# SCH_Self-balancing_2024-06-14.net
KiCad netlist of a schematic drawn in EasyEDA
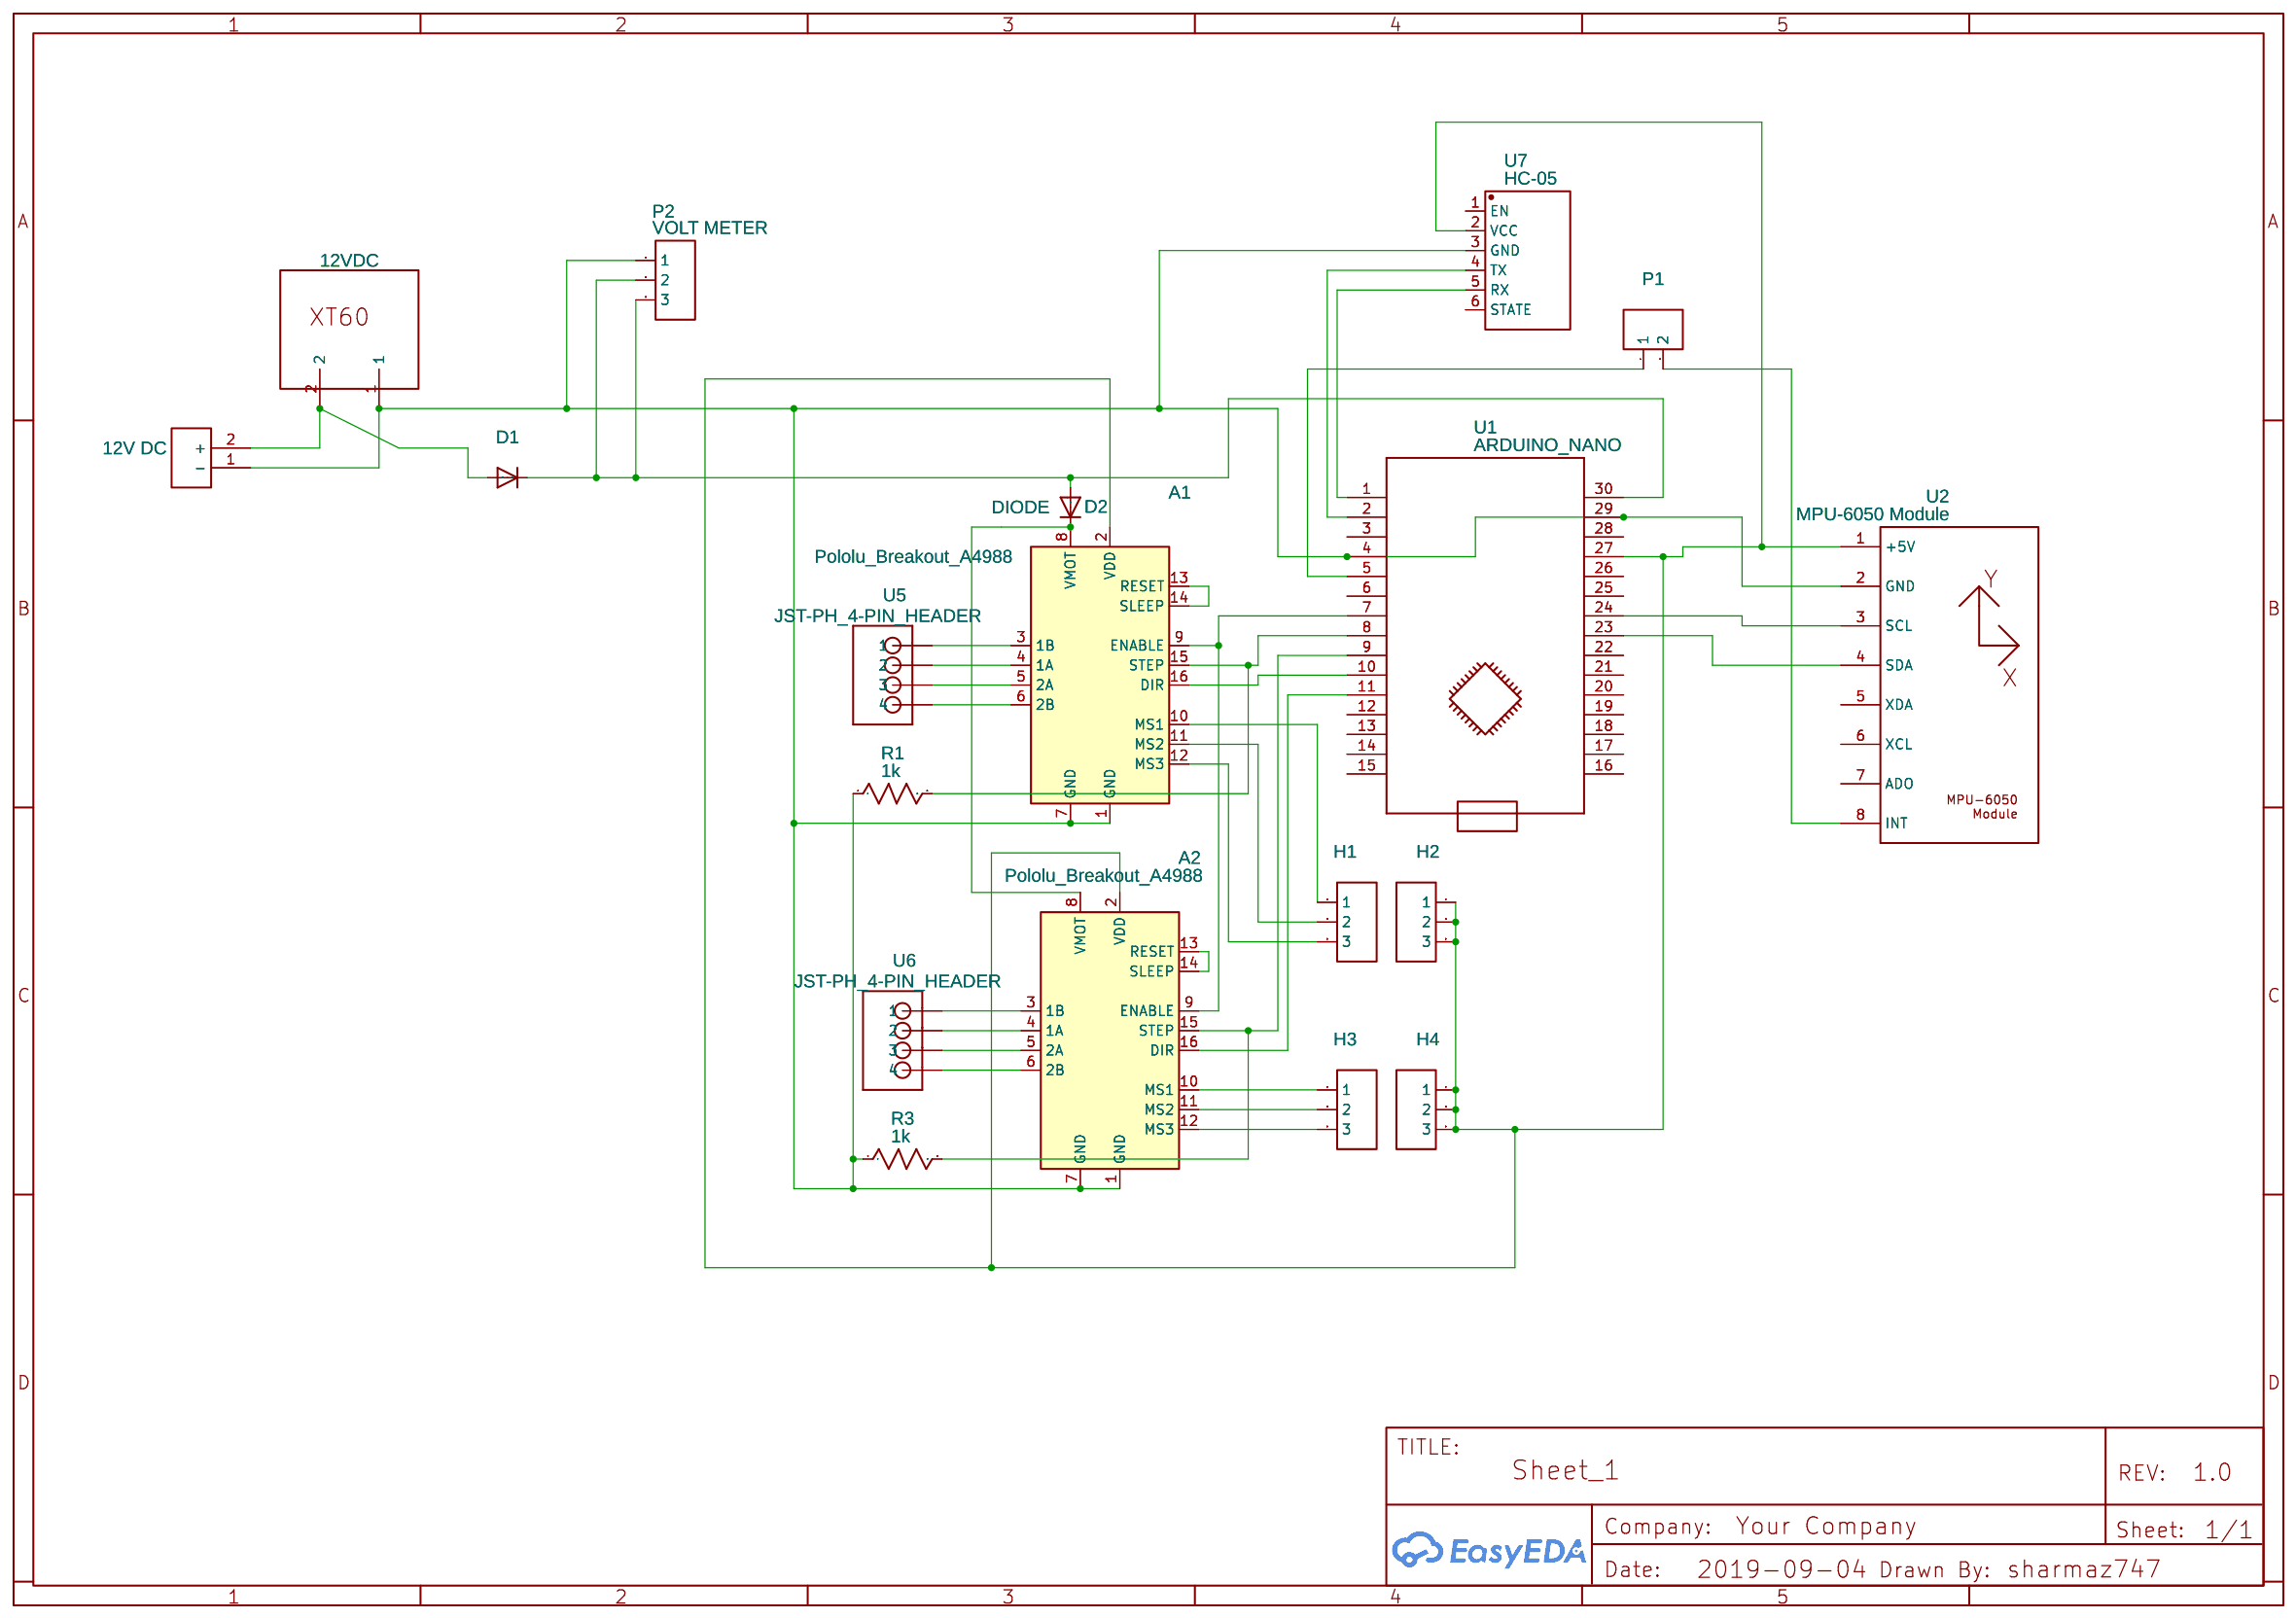
[diagram p0: schematic sheet]

(export (version "E")
  (design (tool "Eeschema 10.0.6"))
  (components
    (comp (ref "12VDC") (value "XT60") (libsource (lib "") (part "Unknown_145_200")))
    (comp (ref "24VDC")
      (value "12V DC")
      (fields (field (name "Manufacturer Part") "SCREW TERMINAL 6P .2"))
      (libsource (lib "") (part "Unknown_120_240"))
    )
    (comp (ref "A1") (value "Pololu_Breakout_A4988") (libsource (lib "") (part "Unknown_550_335")))
    (comp (ref "A2") (value "Pololu_Breakout_A4988") (libsource (lib "") (part "Unknown_555_520")))
    (comp (ref "D1") (value "DIODE") (libsource (lib "") (part "Unknown_250_235")))
    (comp (ref "D2") (value "DIODE") (libsource (lib "") (part "Unknown_535_250")))
    (comp (ref "H1")
      (value "Header-Male-2.54_1x3")
      (fields (field (name "Manufacturer Part") "Header2.54mm 1*3P") (field (name "Manufacturer") "BOOMELE"))
      (libsource (lib "") (part "Unknown_675_460"))
    )
    (comp (ref "H2")
      (value "Header-Male-2.54_1x3")
      (fields (field (name "Manufacturer Part") "Header2.54mm 1*3P") (field (name "Manufacturer") "BOOMELE"))
      (libsource (lib "") (part "Unknown_715_460"))
    )
    (comp (ref "H3")
      (value "Header-Male-2.54_1x3")
      (fields (field (name "Manufacturer Part") "Header2.54mm 1*3P") (field (name "Manufacturer") "BOOMELE"))
      (libsource (lib "") (part "Unknown_675_555"))
    )
    (comp (ref "H4")
      (value "Header-Male-2.54_1x3")
      (fields (field (name "Manufacturer Part") "Header2.54mm 1*3P") (field (name "Manufacturer") "BOOMELE"))
      (libsource (lib "") (part "Unknown_715_555"))
    )
    (comp (ref "P1")
      (value "Header-Female-2.54_1x2")
      (fields (field (name "Manufacturer Part") "2.54-1*2PFemale") (field (name "Manufacturer") "BOOMELE"))
      (libsource (lib "") (part "Unknown_830_165"))
    )
    (comp (ref "P2")
      (value "VOLT METER")
      (fields
        (field (name "Manufacturer Part") "Header-Female-2.54_1x3")
        (field (name "Manufacturer") "Boom Precision Elec")
      )
      (libsource (lib "") (part "Unknown_330_135"))
    )
    (comp (ref "R1") (value "1k") (libsource (lib "") (part "Res_AXIAL-0.3(1/8W)_US")))
    (comp (ref "R3") (value "1k") (libsource (lib "") (part "Res_AXIAL-0.3(1/8W)_US")))
    (comp (ref "U1") (value "ARDUINO_NANO") (libsource (lib "") (part "Unknown_745_320")))
    (comp (ref "U2") (value "MPU-6050 Module") (libsource (lib "") (part "Unknown_975_340")))
    (comp (ref "U5") (value "JST-PH_4-PIN_HEADER") (libsource (lib "") (part "Unknown_445_335")))
    (comp (ref "U6") (value "JST-PH_4-PIN_HEADER") (libsource (lib "") (part "Unknown_450_520")))
    (comp (ref "U7") (value "HC-05") (libsource (lib "") (part "Unknown_745_90")))
  )
  (nets
    (net (code "1") (name "Net-(24VDC-+)") (class "Default")
      (node (ref "12VDC") (pin "2") (pinfunction "2_2") (pintype "unspecified"))
      (node (ref "24VDC") (pin "2") (pinfunction "+_2") (pintype "unspecified"))
      (node (ref "D1") (pin "A") (pinfunction "A_A") (pintype "unspecified"))
    )
    (net (code "2") (name "Net-(24VDC--)") (class "Default")
      (node (ref "12VDC") (pin "1") (pinfunction "1_1") (pintype "unspecified"))
      (node (ref "24VDC") (pin "1") (pinfunction "-_1") (pintype "unspecified"))
      (node (ref "A1") (pin "1") (pinfunction "GND_1") (pintype "bidirectional"))
      (node (ref "A1") (pin "7") (pinfunction "GND_7") (pintype "bidirectional"))
      (node (ref "A2") (pin "1") (pinfunction "GND_1") (pintype "bidirectional"))
      (node (ref "A2") (pin "7") (pinfunction "GND_7") (pintype "bidirectional"))
      (node (ref "P2") (pin "1") (pinfunction "1_1") (pintype "input"))
      (node (ref "R1") (pin "1") (pinfunction "1_1") (pintype "unspecified"))
      (node (ref "R3") (pin "1") (pinfunction "1_1") (pintype "unspecified"))
      (node (ref "U1") (pin "29") (pintype "unspecified"))
      (node (ref "U1") (pin "4") (pintype "unspecified"))
      (node (ref "U2") (pin "2") (pinfunction "GND_2") (pintype "unspecified"))
      (node (ref "U7") (pin "3") (pinfunction "GND_3") (pintype "unspecified"))
    )
    (net (code "3") (name "Net-(A1-1A)") (class "Default")
      (node (ref "A1") (pin "4") (pinfunction "1A_4") (pintype "output"))
      (node (ref "U5") (pin "P2") (pinfunction "2_P2") (pintype "unspecified"))
    )
    (net (code "4") (name "Net-(A1-1B)") (class "Default")
      (node (ref "A1") (pin "3") (pinfunction "1B_3") (pintype "output"))
      (node (ref "U5") (pin "P1") (pinfunction "1_P1") (pintype "unspecified"))
    )
    (net (code "5") (name "Net-(A1-2A)") (class "Default")
      (node (ref "A1") (pin "5") (pinfunction "2A_5") (pintype "output"))
      (node (ref "U5") (pin "P3") (pinfunction "3_P3") (pintype "unspecified"))
    )
    (net (code "6") (name "Net-(A1-2B)") (class "Default")
      (node (ref "A1") (pin "6") (pinfunction "2B_6") (pintype "output"))
      (node (ref "U5") (pin "P4") (pinfunction "4_P4") (pintype "unspecified"))
    )
    (net (code "7") (name "Net-(A1-DIR)") (class "Default")
      (node (ref "A1") (pin "16") (pinfunction "DIR_16") (pintype "input"))
      (node (ref "U1") (pin "10") (pintype "unspecified"))
    )
    (net (code "8") (name "Net-(A1-ENABLE)") (class "Default")
      (node (ref "A1") (pin "9") (pinfunction "ENABLE_9") (pintype "input"))
      (node (ref "A2") (pin "9") (pinfunction "ENABLE_9") (pintype "input"))
      (node (ref "U1") (pin "7") (pintype "unspecified"))
    )
    (net (code "9") (name "Net-(A1-MS1)") (class "Default")
      (node (ref "A1") (pin "10") (pinfunction "MS1_10") (pintype "input"))
      (node (ref "H1") (pin "1") (pinfunction "1_1") (pintype "input"))
    )
    (net (code "10") (name "Net-(A1-MS2)") (class "Default")
      (node (ref "A1") (pin "11") (pinfunction "MS2_11") (pintype "input"))
      (node (ref "H1") (pin "2") (pinfunction "2_2") (pintype "input"))
    )
    (net (code "11") (name "Net-(A1-MS3)") (class "Default")
      (node (ref "A1") (pin "12") (pinfunction "MS3_12") (pintype "input"))
      (node (ref "H1") (pin "3") (pinfunction "3_3") (pintype "input"))
    )
    (net (code "12") (name "Net-(A1-RESET)") (class "Default")
      (node (ref "A1") (pin "13") (pinfunction "RESET_13") (pintype "input"))
      (node (ref "A1") (pin "14") (pinfunction "SLEEP_14") (pintype "input"))
    )
    (net (code "13") (name "Net-(A1-STEP)") (class "Default")
      (node (ref "A1") (pin "15") (pinfunction "STEP_15") (pintype "input"))
      (node (ref "R1") (pin "2") (pinfunction "2_2") (pintype "unspecified"))
      (node (ref "U1") (pin "8") (pintype "unspecified"))
    )
    (net (code "14") (name "Net-(A1-VDD)") (class "Default")
      (node (ref "A1") (pin "2") (pinfunction "VDD_2") (pintype "bidirectional"))
      (node (ref "A2") (pin "2") (pinfunction "VDD_2") (pintype "bidirectional"))
      (node (ref "H2") (pin "1") (pinfunction "1_1") (pintype "input"))
      (node (ref "H2") (pin "2") (pinfunction "2_2") (pintype "input"))
      (node (ref "H2") (pin "3") (pinfunction "3_3") (pintype "input"))
      (node (ref "H4") (pin "1") (pinfunction "1_1") (pintype "input"))
      (node (ref "H4") (pin "2") (pinfunction "2_2") (pintype "input"))
      (node (ref "H4") (pin "3") (pinfunction "3_3") (pintype "input"))
      (node (ref "U1") (pin "27") (pintype "unspecified"))
      (node (ref "U2") (pin "1") (pinfunction "+5V_1") (pintype "unspecified"))
      (node (ref "U7") (pin "2") (pinfunction "VCC_2") (pintype "unspecified"))
    )
    (net (code "15") (name "Net-(A1-VMOT)") (class "Default")
      (node (ref "A1") (pin "8") (pinfunction "VMOT_8") (pintype "bidirectional"))
      (node (ref "A2") (pin "8") (pinfunction "VMOT_8") (pintype "bidirectional"))
      (node (ref "D2") (pin "C") (pinfunction "C_C") (pintype "unspecified"))
    )
    (net (code "16") (name "Net-(A2-1A)") (class "Default")
      (node (ref "A2") (pin "4") (pinfunction "1A_4") (pintype "output"))
      (node (ref "U6") (pin "P2") (pinfunction "2_P2") (pintype "unspecified"))
    )
    (net (code "17") (name "Net-(A2-1B)") (class "Default")
      (node (ref "A2") (pin "3") (pinfunction "1B_3") (pintype "output"))
      (node (ref "U6") (pin "P1") (pinfunction "1_P1") (pintype "unspecified"))
    )
    (net (code "18") (name "Net-(A2-2A)") (class "Default")
      (node (ref "A2") (pin "5") (pinfunction "2A_5") (pintype "output"))
      (node (ref "U6") (pin "P3") (pinfunction "3_P3") (pintype "unspecified"))
    )
    (net (code "19") (name "Net-(A2-2B)") (class "Default")
      (node (ref "A2") (pin "6") (pinfunction "2B_6") (pintype "output"))
      (node (ref "U6") (pin "P4") (pinfunction "4_P4") (pintype "unspecified"))
    )
    (net (code "20") (name "Net-(A2-DIR)") (class "Default")
      (node (ref "A2") (pin "16") (pinfunction "DIR_16") (pintype "input"))
      (node (ref "U1") (pin "11") (pintype "unspecified"))
    )
    (net (code "21") (name "Net-(A2-MS1)") (class "Default")
      (node (ref "A2") (pin "10") (pinfunction "MS1_10") (pintype "input"))
      (node (ref "H3") (pin "1") (pinfunction "1_1") (pintype "input"))
    )
    (net (code "22") (name "Net-(A2-MS2)") (class "Default")
      (node (ref "A2") (pin "11") (pinfunction "MS2_11") (pintype "input"))
      (node (ref "H3") (pin "2") (pinfunction "2_2") (pintype "input"))
    )
    (net (code "23") (name "Net-(A2-MS3)") (class "Default")
      (node (ref "A2") (pin "12") (pinfunction "MS3_12") (pintype "input"))
      (node (ref "H3") (pin "3") (pinfunction "3_3") (pintype "input"))
    )
    (net (code "24") (name "Net-(A2-RESET)") (class "Default")
      (node (ref "A2") (pin "13") (pinfunction "RESET_13") (pintype "input"))
      (node (ref "A2") (pin "14") (pinfunction "SLEEP_14") (pintype "input"))
    )
    (net (code "25") (name "Net-(A2-STEP)") (class "Default")
      (node (ref "A2") (pin "15") (pinfunction "STEP_15") (pintype "input"))
      (node (ref "R3") (pin "2") (pinfunction "2_2") (pintype "unspecified"))
      (node (ref "U1") (pin "9") (pintype "unspecified"))
    )
    (net (code "26") (name "Net-(D1-PadC)") (class "Default")
      (node (ref "D1") (pin "C") (pinfunction "C_C") (pintype "unspecified"))
      (node (ref "D2") (pin "A") (pinfunction "A_A") (pintype "unspecified"))
      (node (ref "P2") (pin "2") (pinfunction "2_2") (pintype "input"))
      (node (ref "P2") (pin "3") (pinfunction "3_3") (pintype "input"))
      (node (ref "U1") (pin "30") (pintype "unspecified"))
    )
    (net (code "27") (name "Net-(P1-Pad1)") (class "Default")
      (node (ref "P1") (pin "1") (pinfunction "1_1") (pintype "input"))
      (node (ref "U1") (pin "5") (pintype "unspecified"))
    )
    (net (code "28") (name "Net-(U2-INT)") (class "Default")
      (node (ref "P1") (pin "2") (pinfunction "2_2") (pintype "input"))
      (node (ref "U2") (pin "8") (pinfunction "INT_8") (pintype "unspecified"))
    )
    (net (code "29") (name "Net-(U2-SCL)") (class "Default")
      (node (ref "U1") (pin "24") (pintype "unspecified"))
      (node (ref "U2") (pin "3") (pinfunction "SCL_3") (pintype "unspecified"))
    )
    (net (code "30") (name "Net-(U2-SDA)") (class "Default")
      (node (ref "U1") (pin "23") (pintype "unspecified"))
      (node (ref "U2") (pin "4") (pinfunction "SDA_4") (pintype "unspecified"))
    )
    (net (code "31") (name "Net-(U7-RX)") (class "Default")
      (node (ref "U1") (pin "1") (pintype "unspecified"))
      (node (ref "U7") (pin "5") (pinfunction "RX_5") (pintype "unspecified"))
    )
    (net (code "32") (name "Net-(U7-TX)") (class "Default")
      (node (ref "U1") (pin "2") (pintype "unspecified"))
      (node (ref "U7") (pin "4") (pinfunction "TX_4") (pintype "unspecified"))
    )
    (net (code "33") (name "unconnected-(U1-Pad3)") (class "Default")
      (node (ref "U1") (pin "3") (pintype "unspecified"))
    )
    (net (code "34") (name "unconnected-(U1-Pad6)") (class "Default")
      (node (ref "U1") (pin "6") (pintype "unspecified"))
    )
    (net (code "35") (name "unconnected-(U1-Pad12)") (class "Default")
      (node (ref "U1") (pin "12") (pintype "unspecified"))
    )
    (net (code "36") (name "unconnected-(U1-Pad13)") (class "Default")
      (node (ref "U1") (pin "13") (pintype "unspecified"))
    )
    (net (code "37") (name "unconnected-(U1-Pad14)") (class "Default")
      (node (ref "U1") (pin "14") (pintype "unspecified"))
    )
    (net (code "38") (name "unconnected-(U1-Pad15)") (class "Default")
      (node (ref "U1") (pin "15") (pintype "unspecified"))
    )
    (net (code "39") (name "unconnected-(U1-Pad16)") (class "Default")
      (node (ref "U1") (pin "16") (pintype "unspecified"))
    )
    (net (code "40") (name "unconnected-(U1-Pad17)") (class "Default")
      (node (ref "U1") (pin "17") (pintype "unspecified"))
    )
    (net (code "41") (name "unconnected-(U1-Pad18)") (class "Default")
      (node (ref "U1") (pin "18") (pintype "unspecified"))
    )
    (net (code "42") (name "unconnected-(U1-Pad19)") (class "Default")
      (node (ref "U1") (pin "19") (pintype "unspecified"))
    )
    (net (code "43") (name "unconnected-(U1-Pad20)") (class "Default")
      (node (ref "U1") (pin "20") (pintype "unspecified"))
    )
    (net (code "44") (name "unconnected-(U1-Pad21)") (class "Default")
      (node (ref "U1") (pin "21") (pintype "unspecified"))
    )
    (net (code "45") (name "unconnected-(U1-Pad22)") (class "Default")
      (node (ref "U1") (pin "22") (pintype "unspecified"))
    )
    (net (code "46") (name "unconnected-(U1-Pad25)") (class "Default")
      (node (ref "U1") (pin "25") (pintype "unspecified"))
    )
    (net (code "47") (name "unconnected-(U1-Pad26)") (class "Default")
      (node (ref "U1") (pin "26") (pintype "unspecified"))
    )
    (net (code "48") (name "unconnected-(U1-Pad28)") (class "Default")
      (node (ref "U1") (pin "28") (pintype "unspecified"))
    )
    (net (code "49") (name "unconnected-(U2-ADO-Pad7)") (class "Default")
      (node (ref "U2") (pin "7") (pinfunction "ADO_7") (pintype "unspecified"))
    )
    (net (code "50") (name "unconnected-(U2-XCL-Pad6)") (class "Default")
      (node (ref "U2") (pin "6") (pinfunction "XCL_6") (pintype "unspecified"))
    )
    (net (code "51") (name "unconnected-(U2-XDA-Pad5)") (class "Default")
      (node (ref "U2") (pin "5") (pinfunction "XDA_5") (pintype "unspecified"))
    )
    (net (code "52") (name "unconnected-(U7-EN-Pad1)") (class "Default")
      (node (ref "U7") (pin "1") (pinfunction "EN_1") (pintype "unspecified"))
    )
    (net (code "53") (name "unconnected-(U7-STATE-Pad6)") (class "Default")
      (node (ref "U7") (pin "6") (pinfunction "STATE_6") (pintype "unspecified"))
    )
  )
)
